# SDRAM.net
KiCad netlist of a schematic drawn in Altium Designer
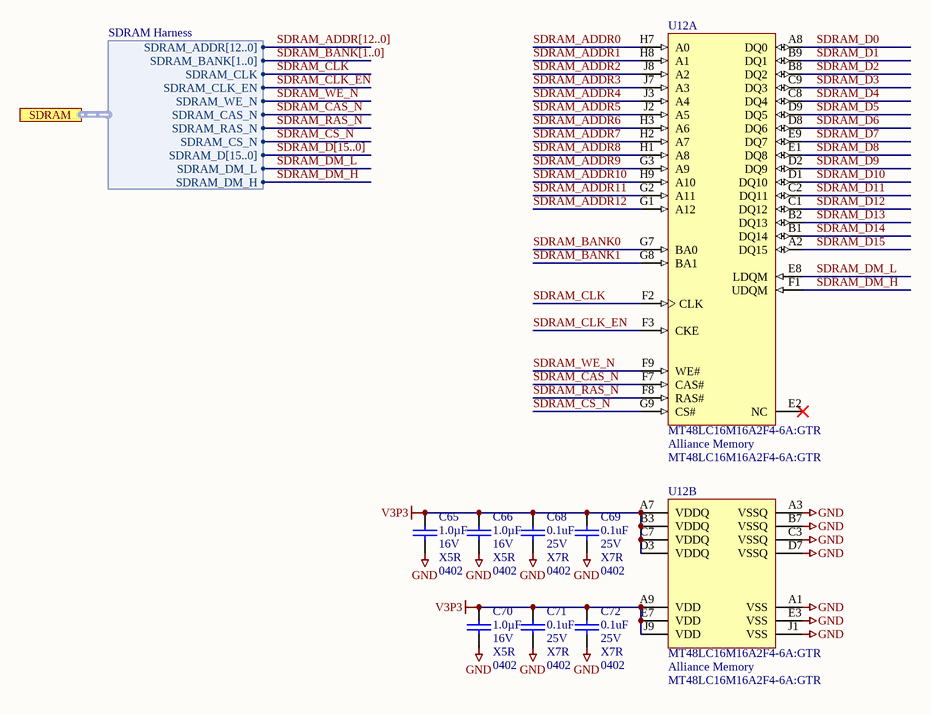
[diagram p0: SDRAM.SchDoc]

(export (version "E")
  (design (tool "Eeschema 10.0.6"))
  (components
    (comp (ref "C65")
      (value "1.0uF")
      (footprint "C_0402")
      (description "CAP CER 1.0UF 16V X5R 0402")
      (fields
        (field (name "TOLERANCE") "10%")
        (field (name "VOLTAGE") "16V")
        (field (name "CAPACITANCE") "1.0µF")
        (field (name "VOLTAGE - RATED") "16V")
        (field (name "TEMPERATURE COEFFICIENT") "X5R")
        (field (name "PACKAGE / CASE") "0402")
      )
      (libsource (lib "Main Library") (part "C_0402_1.0UF_16V"))
    )
    (comp (ref "C66")
      (value "1.0uF")
      (footprint "C_0402")
      (description "CAP CER 1.0UF 16V X5R 0402")
      (fields
        (field (name "TOLERANCE") "10%")
        (field (name "VOLTAGE") "16V")
        (field (name "CAPACITANCE") "1.0µF")
        (field (name "VOLTAGE - RATED") "16V")
        (field (name "TEMPERATURE COEFFICIENT") "X5R")
        (field (name "PACKAGE / CASE") "0402")
      )
      (libsource (lib "Main Library") (part "C_0402_1.0UF_16V"))
    )
    (comp (ref "C68")
      (value "C_0402_0.1UF_25V")
      (footprint "C_0402")
      (description "CAP CER 0.1UF 25V X6S 0402")
      (fields
        (field (name "TOLERANCE") "10%")
        (field (name "CAPACITANCE") "0.1uF")
        (field (name "VOLTAGE - RATED") "25V")
        (field (name "TEMPERATURE COEFFICIENT") "X7R")
        (field (name "PACKAGE / CASE") "0402")
      )
      (libsource (lib "Cospan Design") (part "C_0402_0.1UF_25V"))
    )
    (comp (ref "C69")
      (value "C_0402_0.1UF_25V")
      (footprint "C_0402")
      (description "CAP CER 0.1UF 25V X6S 0402")
      (fields
        (field (name "TOLERANCE") "10%")
        (field (name "CAPACITANCE") "0.1uF")
        (field (name "VOLTAGE - RATED") "25V")
        (field (name "TEMPERATURE COEFFICIENT") "X7R")
        (field (name "PACKAGE / CASE") "0402")
      )
      (libsource (lib "Cospan Design") (part "C_0402_0.1UF_25V"))
    )
    (comp (ref "C70")
      (value "1.0uF")
      (footprint "C_0402")
      (description "CAP CER 1.0UF 16V X5R 0402")
      (fields
        (field (name "TOLERANCE") "10%")
        (field (name "VOLTAGE") "16V")
        (field (name "CAPACITANCE") "1.0µF")
        (field (name "VOLTAGE - RATED") "16V")
        (field (name "TEMPERATURE COEFFICIENT") "X5R")
        (field (name "PACKAGE / CASE") "0402")
      )
      (libsource (lib "Main Library") (part "C_0402_1.0UF_16V"))
    )
    (comp (ref "C71")
      (value "C_0402_0.1UF_25V")
      (footprint "C_0402")
      (description "CAP CER 0.1UF 25V X6S 0402")
      (fields
        (field (name "TOLERANCE") "10%")
        (field (name "CAPACITANCE") "0.1uF")
        (field (name "VOLTAGE - RATED") "25V")
        (field (name "TEMPERATURE COEFFICIENT") "X7R")
        (field (name "PACKAGE / CASE") "0402")
      )
      (libsource (lib "Cospan Design") (part "C_0402_0.1UF_25V"))
    )
    (comp (ref "C72")
      (value "C_0402_0.1UF_25V")
      (footprint "C_0402")
      (description "CAP CER 0.1UF 25V X6S 0402")
      (fields
        (field (name "TOLERANCE") "10%")
        (field (name "CAPACITANCE") "0.1uF")
        (field (name "VOLTAGE - RATED") "25V")
        (field (name "TEMPERATURE COEFFICIENT") "X7R")
        (field (name "PACKAGE / CASE") "0402")
      )
      (libsource (lib "Cospan Design") (part "C_0402_0.1UF_25V"))
    )
    (comp (ref "U12")
      (value "MT48LC16M16A2F4-6A:GTR")
      (footprint "MICT-B4-54")
      (description "256Mb PC133 SDR SDRAM, 16Mb x 16, 6ns, 3.3V, 0 to 70 degC, 54-Ball VFBGA, Pb-Free")
      (fields
        (field (name "MANUFACTURER 1") "Alliance Memory")
        (field (name "MANUFACTURER PART NUMBER 1") "MT48LC16M16A2F4-6A:GTR")
      )
      (libsource (lib "Cospan Design") (part "U_MT48LC16M16A2F4-6A"))
    )
  )
  (nets
    (net (code "3") (name "/SDRAM_ADDR0") (class "Default")
      (node (ref "U12") (pin "H7") (pinfunction "A0_H7") (pintype "input"))
    )
    (net (code "4") (name "/SDRAM_ADDR1") (class "Default")
      (node (ref "U12") (pin "H8") (pinfunction "A1_H8") (pintype "input"))
    )
    (net (code "5") (name "/SDRAM_ADDR2") (class "Default")
      (node (ref "U12") (pin "J8") (pinfunction "A2_J8") (pintype "input"))
    )
    (net (code "6") (name "/SDRAM_ADDR3") (class "Default")
      (node (ref "U12") (pin "J7") (pinfunction "A3_J7") (pintype "input"))
    )
    (net (code "7") (name "/SDRAM_ADDR4") (class "Default")
      (node (ref "U12") (pin "J3") (pinfunction "A4_J3") (pintype "input"))
    )
    (net (code "8") (name "/SDRAM_ADDR5") (class "Default")
      (node (ref "U12") (pin "J2") (pinfunction "A5_J2") (pintype "input"))
    )
    (net (code "9") (name "/SDRAM_ADDR6") (class "Default")
      (node (ref "U12") (pin "H3") (pinfunction "A6_H3") (pintype "input"))
    )
    (net (code "10") (name "/SDRAM_ADDR7") (class "Default")
      (node (ref "U12") (pin "H2") (pinfunction "A7_H2") (pintype "input"))
    )
    (net (code "11") (name "/SDRAM_ADDR8") (class "Default")
      (node (ref "U12") (pin "H1") (pinfunction "A8_H1") (pintype "input"))
    )
    (net (code "12") (name "/SDRAM_ADDR9") (class "Default")
      (node (ref "U12") (pin "G3") (pinfunction "A9_G3") (pintype "input"))
    )
    (net (code "13") (name "/SDRAM_ADDR10") (class "Default")
      (node (ref "U12") (pin "H9") (pinfunction "A10_H9") (pintype "input"))
    )
    (net (code "14") (name "/SDRAM_ADDR11") (class "Default")
      (node (ref "U12") (pin "G2") (pinfunction "A11_G2") (pintype "input"))
    )
    (net (code "15") (name "/SDRAM_ADDR12") (class "Default")
      (node (ref "U12") (pin "G1") (pinfunction "A12_G1") (pintype "input"))
    )
    (net (code "17") (name "/SDRAM_BANK0") (class "Default")
      (node (ref "U12") (pin "G7") (pinfunction "BA0_G7") (pintype "input"))
    )
    (net (code "18") (name "/SDRAM_BANK1") (class "Default")
      (node (ref "U12") (pin "G8") (pinfunction "BA1_G8") (pintype "input"))
    )
    (net (code "20") (name "/SDRAM_CAS_N") (class "Default")
      (node (ref "U12") (pin "F7") (pinfunction "CAS#_F7") (pintype "input"))
    )
    (net (code "21") (name "/SDRAM_CLK") (class "Default")
      (node (ref "U12") (pin "F2") (pinfunction "CLK_F2") (pintype "input"))
    )
    (net (code "22") (name "/SDRAM_CLK_EN") (class "Default")
      (node (ref "U12") (pin "F3") (pinfunction "CKE_F3") (pintype "input"))
    )
    (net (code "23") (name "/SDRAM_CS_N") (class "Default")
      (node (ref "U12") (pin "G9") (pinfunction "CS#_G9") (pintype "input"))
    )
    (net (code "24") (name "/SDRAM_D0") (class "Default")
      (node (ref "U12") (pin "A8") (pinfunction "DQ0_A8") (pintype "bidirectional"))
    )
    (net (code "25") (name "/SDRAM_D1") (class "Default")
      (node (ref "U12") (pin "B9") (pinfunction "DQ1_B9") (pintype "bidirectional"))
    )
    (net (code "26") (name "/SDRAM_D2") (class "Default")
      (node (ref "U12") (pin "B8") (pinfunction "DQ2_B8") (pintype "bidirectional"))
    )
    (net (code "27") (name "/SDRAM_D3") (class "Default")
      (node (ref "U12") (pin "C9") (pinfunction "DQ3_C9") (pintype "bidirectional"))
    )
    (net (code "28") (name "/SDRAM_D4") (class "Default")
      (node (ref "U12") (pin "C8") (pinfunction "DQ4_C8") (pintype "bidirectional"))
    )
    (net (code "29") (name "/SDRAM_D5") (class "Default")
      (node (ref "U12") (pin "D9") (pinfunction "DQ5_D9") (pintype "bidirectional"))
    )
    (net (code "30") (name "/SDRAM_D6") (class "Default")
      (node (ref "U12") (pin "D8") (pinfunction "DQ6_D8") (pintype "bidirectional"))
    )
    (net (code "31") (name "/SDRAM_D7") (class "Default")
      (node (ref "U12") (pin "E9") (pinfunction "DQ7_E9") (pintype "bidirectional"))
    )
    (net (code "32") (name "/SDRAM_D8") (class "Default")
      (node (ref "U12") (pin "E1") (pinfunction "DQ8_E1") (pintype "bidirectional"))
    )
    (net (code "33") (name "/SDRAM_D9") (class "Default")
      (node (ref "U12") (pin "D2") (pinfunction "DQ9_D2") (pintype "bidirectional"))
    )
    (net (code "34") (name "/SDRAM_D10") (class "Default")
      (node (ref "U12") (pin "D1") (pinfunction "DQ10_D1") (pintype "bidirectional"))
    )
    (net (code "35") (name "/SDRAM_D11") (class "Default")
      (node (ref "U12") (pin "C2") (pinfunction "DQ11_C2") (pintype "bidirectional"))
    )
    (net (code "36") (name "/SDRAM_D12") (class "Default")
      (node (ref "U12") (pin "C1") (pinfunction "DQ12_C1") (pintype "bidirectional"))
    )
    (net (code "37") (name "/SDRAM_D13") (class "Default")
      (node (ref "U12") (pin "B2") (pinfunction "DQ13_B2") (pintype "bidirectional"))
    )
    (net (code "38") (name "/SDRAM_D14") (class "Default")
      (node (ref "U12") (pin "B1") (pinfunction "DQ14_B1") (pintype "bidirectional"))
    )
    (net (code "39") (name "/SDRAM_D15") (class "Default")
      (node (ref "U12") (pin "A2") (pinfunction "DQ15_A2") (pintype "bidirectional"))
    )
    (net (code "40") (name "/SDRAM_DM_H") (class "Default")
      (node (ref "U12") (pin "F1") (pinfunction "UDQM_F1") (pintype "input"))
    )
    (net (code "41") (name "/SDRAM_DM_L") (class "Default")
      (node (ref "U12") (pin "E8") (pinfunction "LDQM_E8") (pintype "input"))
    )
    (net (code "43") (name "/SDRAM_RAS_N") (class "Default")
      (node (ref "U12") (pin "F8") (pinfunction "RAS#_F8") (pintype "input"))
    )
    (net (code "44") (name "/SDRAM_WE_N") (class "Default")
      (node (ref "U12") (pin "F9") (pinfunction "WE#_F9") (pintype "input"))
    )
    (net (code "46") (name "GND") (class "Default")
      (node (ref "C65") (pin "1") (pinfunction "1_1") (pintype "passive"))
      (node (ref "C66") (pin "1") (pinfunction "1_1") (pintype "passive"))
      (node (ref "C68") (pin "1") (pinfunction "1_1") (pintype "passive"))
      (node (ref "C69") (pin "1") (pinfunction "1_1") (pintype "passive"))
      (node (ref "C70") (pin "1") (pinfunction "1_1") (pintype "passive"))
      (node (ref "C71") (pin "1") (pinfunction "1_1") (pintype "passive"))
      (node (ref "C72") (pin "1") (pinfunction "1_1") (pintype "passive"))
      (node (ref "U12") (pin "A1") (pinfunction "VSS_A1") (pintype "power_in"))
      (node (ref "U12") (pin "A3") (pinfunction "VSSQ_A3") (pintype "power_in"))
      (node (ref "U12") (pin "B7") (pinfunction "VSSQ_B7") (pintype "power_in"))
      (node (ref "U12") (pin "C3") (pinfunction "VSSQ_C3") (pintype "power_in"))
      (node (ref "U12") (pin "D7") (pinfunction "VSSQ_D7") (pintype "power_in"))
      (node (ref "U12") (pin "E3") (pinfunction "VSS_E3") (pintype "power_in"))
      (node (ref "U12") (pin "J1") (pinfunction "VSS_J1") (pintype "power_in"))
    )
    (net (code "47") (name "V3P3") (class "Default")
      (node (ref "C65") (pin "2") (pinfunction "2_2") (pintype "passive"))
      (node (ref "C66") (pin "2") (pinfunction "2_2") (pintype "passive"))
      (node (ref "C68") (pin "2") (pinfunction "2_2") (pintype "passive"))
      (node (ref "C69") (pin "2") (pinfunction "2_2") (pintype "passive"))
      (node (ref "C70") (pin "2") (pinfunction "2_2") (pintype "passive"))
      (node (ref "C71") (pin "2") (pinfunction "2_2") (pintype "passive"))
      (node (ref "C72") (pin "2") (pinfunction "2_2") (pintype "passive"))
      (node (ref "U12") (pin "A7") (pinfunction "VDDQ_A7") (pintype "power_in"))
      (node (ref "U12") (pin "A9") (pinfunction "VDD_A9") (pintype "power_in"))
      (node (ref "U12") (pin "B3") (pinfunction "VDDQ_B3") (pintype "power_in"))
      (node (ref "U12") (pin "C7") (pinfunction "VDDQ_C7") (pintype "power_in"))
      (node (ref "U12") (pin "D3") (pinfunction "VDDQ_D3") (pintype "power_in"))
      (node (ref "U12") (pin "E7") (pinfunction "VDD_E7") (pintype "power_in"))
      (node (ref "U12") (pin "J9") (pinfunction "VDD_J9") (pintype "power_in"))
    )
    (net (code "48") (name "unconnected-(U12A-NC-PadE2)") (class "Default")
      (node (ref "U12") (pin "E2") (pinfunction "NC_E2") (pintype "passive+no_connect"))
    )
  )
)
